# univ_3-1-0-x-rev2.net
KiCad netlist of a schematic drawn in EAGLE
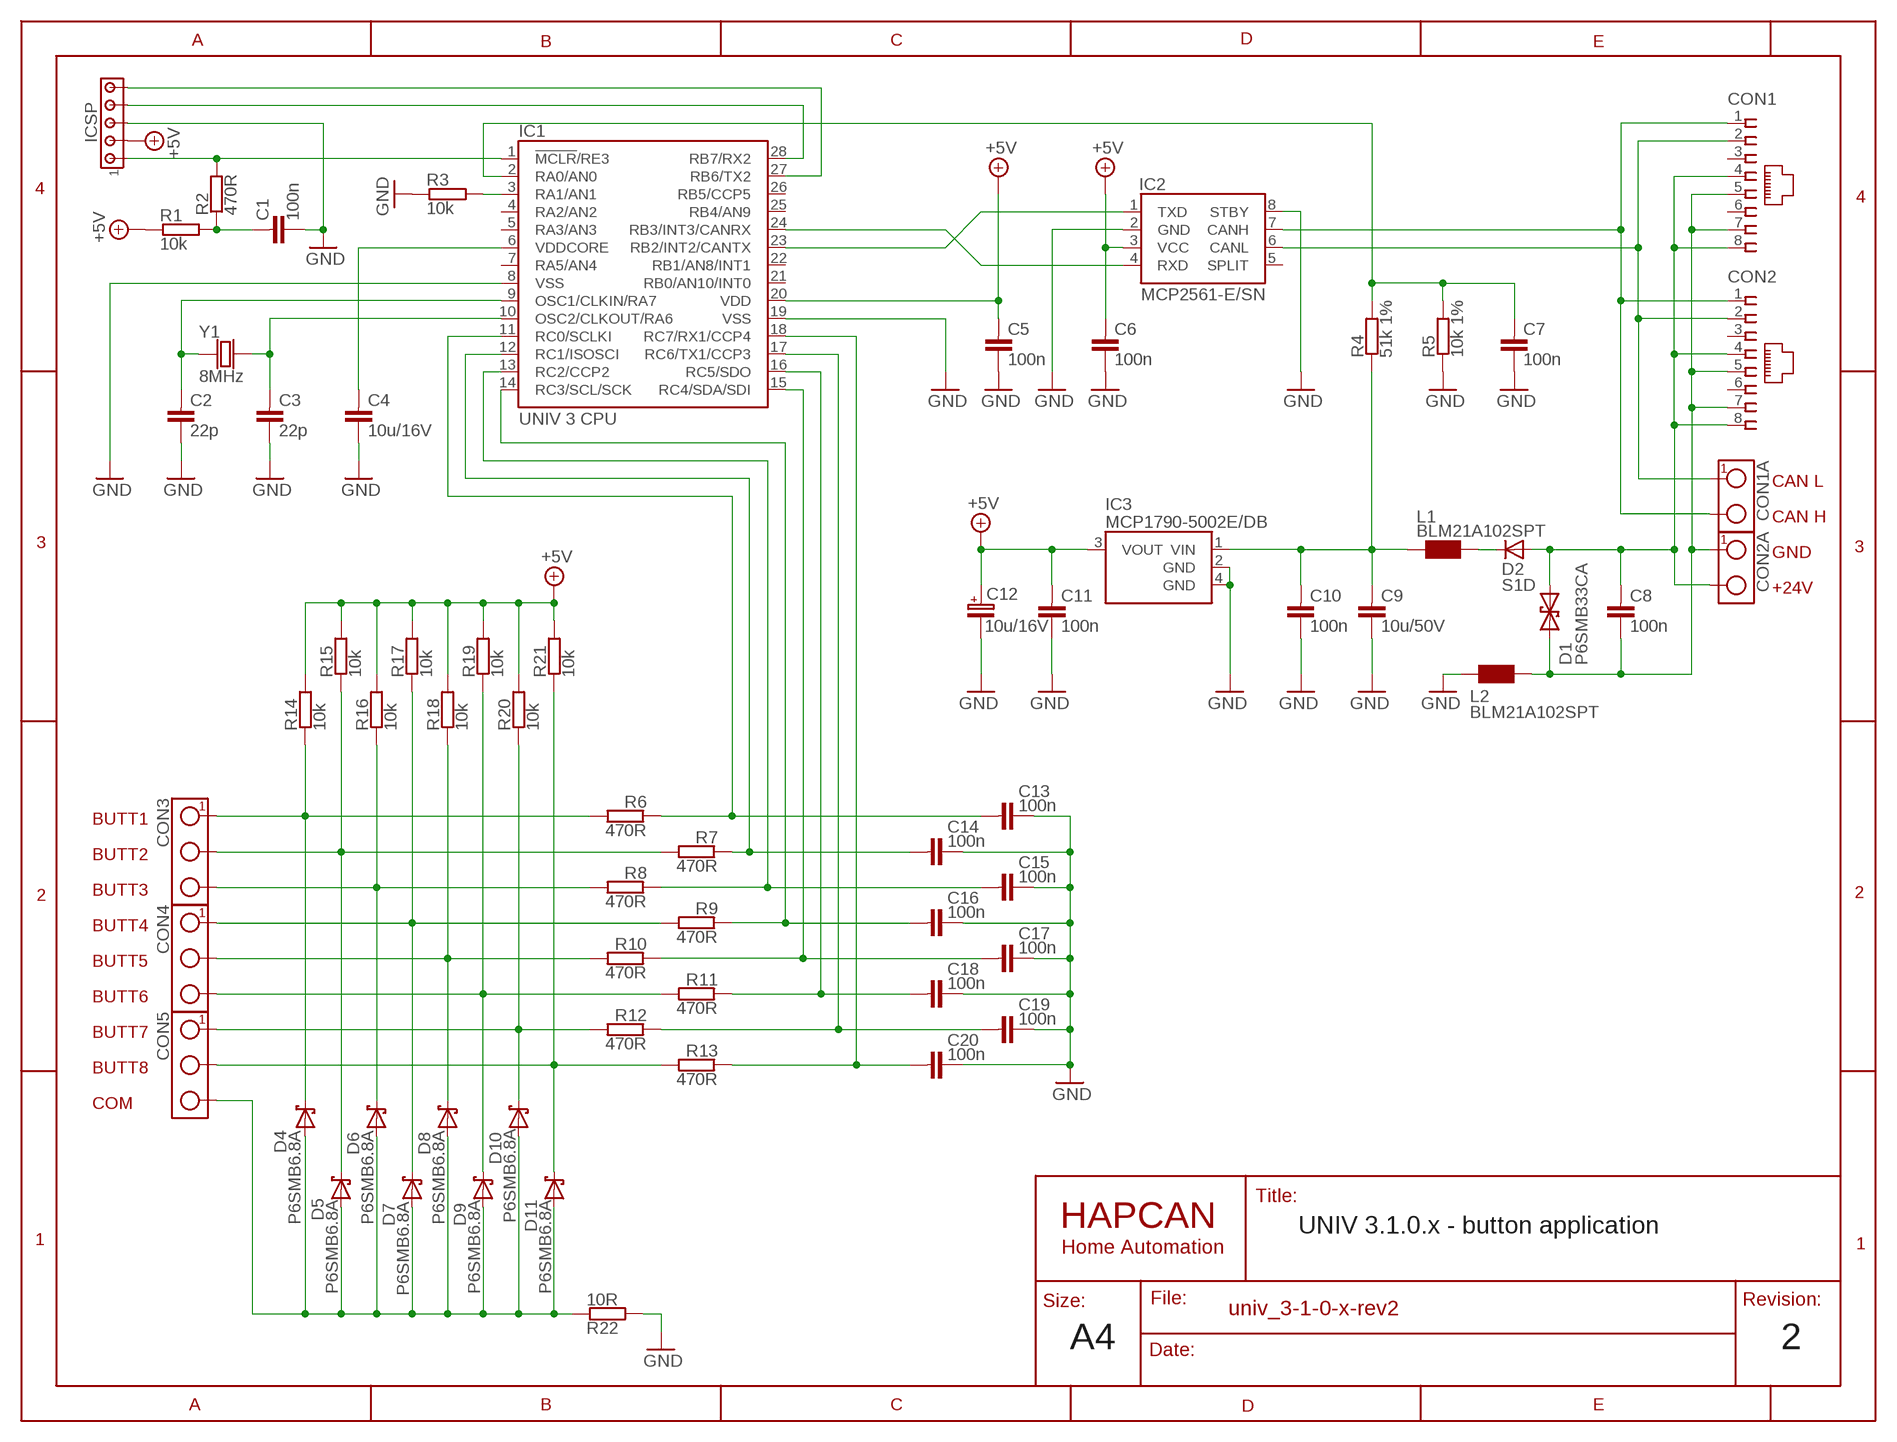
[diagram p0: schematic, sheet 1]

(export (version "E")
  (design (tool "Eeschema 10.0.6"))
  (components
    (comp (ref "C1")
      (value "100n")
      (footprint "eagle-import:0805")
      (libsource (lib "eagle-import") (part "CAPACITOR0805"))
    )
    (comp (ref "C2")
      (value "22p")
      (footprint "eagle-import:0805")
      (libsource (lib "eagle-import") (part "CAPACITOR0805"))
    )
    (comp (ref "C3")
      (value "22p")
      (footprint "eagle-import:0805")
      (libsource (lib "eagle-import") (part "CAPACITOR0805"))
    )
    (comp (ref "C4")
      (value "10u/16V")
      (footprint "eagle-import:0805")
      (libsource (lib "eagle-import") (part "CAPACITOR0805"))
    )
    (comp (ref "C5")
      (value "100n")
      (footprint "eagle-import:0805")
      (libsource (lib "eagle-import") (part "CAPACITOR0805"))
    )
    (comp (ref "C6")
      (value "100n")
      (footprint "eagle-import:0805")
      (libsource (lib "eagle-import") (part "CAPACITOR0805"))
    )
    (comp (ref "C7")
      (value "100n")
      (footprint "eagle-import:0805")
      (libsource (lib "eagle-import") (part "CAPACITOR0805"))
    )
    (comp (ref "C8")
      (value "100n")
      (footprint "eagle-import:0805")
      (libsource (lib "eagle-import") (part "CAPACITOR0805"))
    )
    (comp (ref "C9")
      (value "10u/50V")
      (footprint "eagle-import:1210")
      (libsource (lib "eagle-import") (part "CAPACITOR1210"))
    )
    (comp (ref "C10")
      (value "100n")
      (footprint "eagle-import:0805")
      (libsource (lib "eagle-import") (part "CAPACITOR0805"))
    )
    (comp (ref "C11")
      (value "100n")
      (footprint "eagle-import:0805")
      (libsource (lib "eagle-import") (part "CAPACITOR0805"))
    )
    (comp (ref "C12")
      (value "10u/16V")
      (footprint "eagle-import:SMC_B")
      (libsource (lib "eagle-import") (part "CAPACITOR-POLARIZED-SMC_B"))
    )
    (comp (ref "C13")
      (value "100n")
      (footprint "eagle-import:0805")
      (libsource (lib "eagle-import") (part "CAPACITOR0805"))
    )
    (comp (ref "C14")
      (value "100n")
      (footprint "eagle-import:0805")
      (libsource (lib "eagle-import") (part "CAPACITOR0805"))
    )
    (comp (ref "C15")
      (value "100n")
      (footprint "eagle-import:0805")
      (libsource (lib "eagle-import") (part "CAPACITOR0805"))
    )
    (comp (ref "C16")
      (value "100n")
      (footprint "eagle-import:0805")
      (libsource (lib "eagle-import") (part "CAPACITOR0805"))
    )
    (comp (ref "C17")
      (value "100n")
      (footprint "eagle-import:0805")
      (libsource (lib "eagle-import") (part "CAPACITOR0805"))
    )
    (comp (ref "C18")
      (value "100n")
      (footprint "eagle-import:0805")
      (libsource (lib "eagle-import") (part "CAPACITOR0805"))
    )
    (comp (ref "C19")
      (value "100n")
      (footprint "eagle-import:0805")
      (libsource (lib "eagle-import") (part "CAPACITOR0805"))
    )
    (comp (ref "C20")
      (value "100n")
      (footprint "eagle-import:0805")
      (libsource (lib "eagle-import") (part "CAPACITOR0805"))
    )
    (comp (ref "CON1")
      (value "RJ45-SOCKET")
      (footprint "eagle-import:RJ45-PCB-SOCKET")
      (libsource (lib "eagle-import") (part "RJ45-SOCKET"))
    )
    (comp (ref "CON1A")
      (value "TERMINAL-2")
      (footprint "eagle-import:ARK2-5X10,5MM")
      (libsource (lib "eagle-import") (part "TERMINAL-2-5X10,5MM"))
    )
    (comp (ref "CON2")
      (value "RJ45-SOCKET")
      (footprint "eagle-import:RJ45-PCB-SOCKET")
      (libsource (lib "eagle-import") (part "RJ45-SOCKET"))
    )
    (comp (ref "CON2A")
      (value "TERMINAL-2")
      (footprint "eagle-import:ARK2-5X10,5MM")
      (libsource (lib "eagle-import") (part "TERMINAL-2-5X10,5MM"))
    )
    (comp (ref "CON3")
      (value "TERMINAL-3")
      (footprint "eagle-import:ARK3-5X10.5MM")
      (libsource (lib "eagle-import") (part "TERMINAL-3-5X10.5MM"))
    )
    (comp (ref "CON4")
      (value "TERMINAL-3")
      (footprint "eagle-import:ARK3-5X10.5MM")
      (libsource (lib "eagle-import") (part "TERMINAL-3-5X10.5MM"))
    )
    (comp (ref "CON5")
      (value "TERMINAL-3")
      (footprint "eagle-import:ARK3-5X10.5MM")
      (libsource (lib "eagle-import") (part "TERMINAL-3-5X10.5MM"))
    )
    (comp (ref "D1")
      (value "P6SMB33CA")
      (footprint "eagle-import:DO-214_TRANSIL2")
      (libsource (lib "eagle-import") (part "DIODE_TRANSIL2"))
    )
    (comp (ref "D2")
      (value "S1D")
      (footprint "eagle-import:DO-214")
      (libsource (lib "eagle-import") (part "DIODE_DO-214"))
    )
    (comp (ref "D4")
      (value "P6SMB6.8A")
      (footprint "eagle-import:DO-214")
      (libsource (lib "eagle-import") (part "DIODE_TRANSIL1_DO214"))
    )
    (comp (ref "D5")
      (value "P6SMB6.8A")
      (footprint "eagle-import:DO-214")
      (libsource (lib "eagle-import") (part "DIODE_TRANSIL1_DO214"))
    )
    (comp (ref "D6")
      (value "P6SMB6.8A")
      (footprint "eagle-import:DO-214")
      (libsource (lib "eagle-import") (part "DIODE_TRANSIL1_DO214"))
    )
    (comp (ref "D7")
      (value "P6SMB6.8A")
      (footprint "eagle-import:DO-214")
      (libsource (lib "eagle-import") (part "DIODE_TRANSIL1_DO214"))
    )
    (comp (ref "D8")
      (value "P6SMB6.8A")
      (footprint "eagle-import:DO-214")
      (libsource (lib "eagle-import") (part "DIODE_TRANSIL1_DO214"))
    )
    (comp (ref "D9")
      (value "P6SMB6.8A")
      (footprint "eagle-import:DO-214")
      (libsource (lib "eagle-import") (part "DIODE_TRANSIL1_DO214"))
    )
    (comp (ref "D10")
      (value "P6SMB6.8A")
      (footprint "eagle-import:DO-214")
      (libsource (lib "eagle-import") (part "DIODE_TRANSIL1_DO214"))
    )
    (comp (ref "D11")
      (value "P6SMB6.8A")
      (footprint "eagle-import:DO-214")
      (libsource (lib "eagle-import") (part "DIODE_TRANSIL1_DO214"))
    )
    (comp (ref "IC1")
      (value "UNIV 3 CPU")
      (footprint "eagle-import:UNIV3CPU")
      (libsource (lib "eagle-import") (part "UNIV3CPU-I/SO"))
    )
    (comp (ref "IC2")
      (value "MCP2561-E/SN")
      (footprint "eagle-import:SO-08")
      (libsource (lib "eagle-import") (part "MCP2561-E/SN"))
    )
    (comp (ref "IC3")
      (value "MCP1790-5002E/DB")
      (footprint "eagle-import:SOT-223")
      (libsource (lib "eagle-import") (part "MCP1790"))
    )
    (comp (ref "ICSP")
      (value "HEADER5")
      (footprint "eagle-import:SIP-5")
      (libsource (lib "eagle-import") (part "HEADER5"))
    )
    (comp (ref "L1")
      (value "BLM21A102SPT")
      (footprint "eagle-import:0805")
      (libsource (lib "eagle-import") (part "CHOKE0805"))
    )
    (comp (ref "L2")
      (value "BLM21A102SPT")
      (footprint "eagle-import:0805")
      (libsource (lib "eagle-import") (part "CHOKE0805"))
    )
    (comp (ref "R1")
      (value "10k")
      (footprint "eagle-import:0805")
      (libsource (lib "eagle-import") (part "RESISTOR0805"))
    )
    (comp (ref "R2")
      (value "470R")
      (footprint "eagle-import:0805")
      (libsource (lib "eagle-import") (part "RESISTOR0805"))
    )
    (comp (ref "R3")
      (value "10k")
      (footprint "eagle-import:0805")
      (libsource (lib "eagle-import") (part "RESISTOR0805"))
    )
    (comp (ref "R4")
      (value "51k 1%")
      (footprint "eagle-import:0805")
      (libsource (lib "eagle-import") (part "RESISTOR0805"))
    )
    (comp (ref "R5")
      (value "10k 1%")
      (footprint "eagle-import:0805")
      (libsource (lib "eagle-import") (part "RESISTOR0805"))
    )
    (comp (ref "R6")
      (value "470R")
      (footprint "eagle-import:0805")
      (libsource (lib "eagle-import") (part "RESISTOR0805"))
    )
    (comp (ref "R7")
      (value "470R")
      (footprint "eagle-import:0805")
      (libsource (lib "eagle-import") (part "RESISTOR0805"))
    )
    (comp (ref "R8")
      (value "470R")
      (footprint "eagle-import:0805")
      (libsource (lib "eagle-import") (part "RESISTOR0805"))
    )
    (comp (ref "R9")
      (value "470R")
      (footprint "eagle-import:0805")
      (libsource (lib "eagle-import") (part "RESISTOR0805"))
    )
    (comp (ref "R10")
      (value "470R")
      (footprint "eagle-import:0805")
      (libsource (lib "eagle-import") (part "RESISTOR0805"))
    )
    (comp (ref "R11")
      (value "470R")
      (footprint "eagle-import:0805")
      (libsource (lib "eagle-import") (part "RESISTOR0805"))
    )
    (comp (ref "R12")
      (value "470R")
      (footprint "eagle-import:0805")
      (libsource (lib "eagle-import") (part "RESISTOR0805"))
    )
    (comp (ref "R13")
      (value "470R")
      (footprint "eagle-import:0805")
      (libsource (lib "eagle-import") (part "RESISTOR0805"))
    )
    (comp (ref "R14")
      (value "10k")
      (footprint "eagle-import:0805")
      (libsource (lib "eagle-import") (part "RESISTOR0805"))
    )
    (comp (ref "R15")
      (value "10k")
      (footprint "eagle-import:0805")
      (libsource (lib "eagle-import") (part "RESISTOR0805"))
    )
    (comp (ref "R16")
      (value "10k")
      (footprint "eagle-import:0805")
      (libsource (lib "eagle-import") (part "RESISTOR0805"))
    )
    (comp (ref "R17")
      (value "10k")
      (footprint "eagle-import:0805")
      (libsource (lib "eagle-import") (part "RESISTOR0805"))
    )
    (comp (ref "R18")
      (value "10k")
      (footprint "eagle-import:0805")
      (libsource (lib "eagle-import") (part "RESISTOR0805"))
    )
    (comp (ref "R19")
      (value "10k")
      (footprint "eagle-import:0805")
      (libsource (lib "eagle-import") (part "RESISTOR0805"))
    )
    (comp (ref "R20")
      (value "10k")
      (footprint "eagle-import:0805")
      (libsource (lib "eagle-import") (part "RESISTOR0805"))
    )
    (comp (ref "R21")
      (value "10k")
      (footprint "eagle-import:0805")
      (libsource (lib "eagle-import") (part "RESISTOR0805"))
    )
    (comp (ref "R22")
      (value "10R")
      (footprint "eagle-import:0805")
      (libsource (lib "eagle-import") (part "RESISTOR0805"))
    )
    (comp (ref "Y1")
      (value "8MHz")
      (footprint "eagle-import:CRYSTAL-HC49V")
      (libsource (lib "eagle-import") (part "CRYSTAL-HC49V"))
    )
  )
  (nets
    (net (code "1") (name "+5V") (class "Default")
      (node (ref "C11") (pin "1") (pinfunction "1_1") (pintype "passive"))
      (node (ref "C12") (pin "+") (pinfunction "1_+") (pintype "passive"))
      (node (ref "C5") (pin "1") (pinfunction "1_1") (pintype "passive"))
      (node (ref "C6") (pin "1") (pinfunction "1_1") (pintype "passive"))
      (node (ref "IC1") (pin "20") (pinfunction "VDD_20") (pintype "bidirectional"))
      (node (ref "IC2") (pin "3") (pinfunction "VCC_3") (pintype "bidirectional"))
      (node (ref "IC3") (pin "3") (pinfunction "VOUT_3") (pintype "bidirectional"))
      (node (ref "ICSP") (pin "2") (pinfunction "2_2") (pintype "passive"))
      (node (ref "R1") (pin "1") (pinfunction "1_1") (pintype "passive"))
      (node (ref "R14") (pin "2") (pinfunction "2_2") (pintype "passive"))
      (node (ref "R15") (pin "2") (pinfunction "2_2") (pintype "passive"))
      (node (ref "R16") (pin "2") (pinfunction "2_2") (pintype "passive"))
      (node (ref "R17") (pin "2") (pinfunction "2_2") (pintype "passive"))
      (node (ref "R18") (pin "2") (pinfunction "2_2") (pintype "passive"))
      (node (ref "R19") (pin "2") (pinfunction "2_2") (pintype "passive"))
      (node (ref "R20") (pin "2") (pinfunction "2_2") (pintype "passive"))
      (node (ref "R21") (pin "2") (pinfunction "2_2") (pintype "passive"))
    )
    (net (code "2") (name "GND") (class "Default")
      (node (ref "C1") (pin "2") (pinfunction "2_2") (pintype "passive"))
      (node (ref "C10") (pin "2") (pinfunction "2_2") (pintype "passive"))
      (node (ref "C11") (pin "2") (pinfunction "2_2") (pintype "passive"))
      (node (ref "C12") (pin "-") (pinfunction "2_-") (pintype "passive"))
      (node (ref "C13") (pin "2") (pinfunction "2_2") (pintype "passive"))
      (node (ref "C14") (pin "2") (pinfunction "2_2") (pintype "passive"))
      (node (ref "C15") (pin "2") (pinfunction "2_2") (pintype "passive"))
      (node (ref "C16") (pin "2") (pinfunction "2_2") (pintype "passive"))
      (node (ref "C17") (pin "2") (pinfunction "2_2") (pintype "passive"))
      (node (ref "C18") (pin "2") (pinfunction "2_2") (pintype "passive"))
      (node (ref "C19") (pin "2") (pinfunction "2_2") (pintype "passive"))
      (node (ref "C2") (pin "2") (pinfunction "2_2") (pintype "passive"))
      (node (ref "C20") (pin "2") (pinfunction "2_2") (pintype "passive"))
      (node (ref "C3") (pin "2") (pinfunction "2_2") (pintype "passive"))
      (node (ref "C4") (pin "2") (pinfunction "2_2") (pintype "passive"))
      (node (ref "C5") (pin "2") (pinfunction "2_2") (pintype "passive"))
      (node (ref "C6") (pin "2") (pinfunction "2_2") (pintype "passive"))
      (node (ref "C7") (pin "2") (pinfunction "2_2") (pintype "passive"))
      (node (ref "C9") (pin "2") (pinfunction "2_2") (pintype "passive"))
      (node (ref "IC1") (pin "19") (pinfunction "VSS_19") (pintype "bidirectional"))
      (node (ref "IC1") (pin "8") (pinfunction "VSS_8") (pintype "bidirectional"))
      (node (ref "IC2") (pin "2") (pinfunction "GND_2") (pintype "bidirectional"))
      (node (ref "IC2") (pin "8") (pinfunction "STBY_8") (pintype "bidirectional"))
      (node (ref "IC3") (pin "2") (pinfunction "GND_2") (pintype "bidirectional"))
      (node (ref "IC3") (pin "4") (pinfunction "GND_4") (pintype "bidirectional"))
      (node (ref "ICSP") (pin "3") (pinfunction "3_3") (pintype "passive"))
      (node (ref "L2") (pin "1") (pinfunction "1_1") (pintype "passive"))
      (node (ref "R22") (pin "2") (pinfunction "2_2") (pintype "passive"))
      (node (ref "R3") (pin "1") (pinfunction "1_1") (pintype "passive"))
      (node (ref "R5") (pin "1") (pinfunction "1_1") (pintype "passive"))
    )
    (net (code "3") (name "Net-(C1-Pad1)") (class "Default")
      (node (ref "C1") (pin "1") (pinfunction "1_1") (pintype "passive"))
      (node (ref "R1") (pin "2") (pinfunction "2_2") (pintype "passive"))
      (node (ref "R2") (pin "1") (pinfunction "1_1") (pintype "passive"))
    )
    (net (code "4") (name "Net-(CON3-Pad1)") (class "Default")
      (node (ref "CON3") (pin "1") (pinfunction "1_1") (pintype "passive"))
      (node (ref "D4") (pin "C") (pinfunction "C_C") (pintype "passive"))
      (node (ref "R14") (pin "1") (pinfunction "1_1") (pintype "passive"))
      (node (ref "R6") (pin "2") (pinfunction "2_2") (pintype "passive"))
    )
    (net (code "5") (name "Net-(CON3-Pad2)") (class "Default")
      (node (ref "CON3") (pin "2") (pinfunction "2_2") (pintype "passive"))
      (node (ref "D5") (pin "C") (pinfunction "C_C") (pintype "passive"))
      (node (ref "R15") (pin "1") (pinfunction "1_1") (pintype "passive"))
      (node (ref "R7") (pin "2") (pinfunction "2_2") (pintype "passive"))
    )
    (net (code "6") (name "Net-(CON3-Pad3)") (class "Default")
      (node (ref "CON3") (pin "3") (pinfunction "3_3") (pintype "passive"))
      (node (ref "D6") (pin "C") (pinfunction "C_C") (pintype "passive"))
      (node (ref "R16") (pin "1") (pinfunction "1_1") (pintype "passive"))
      (node (ref "R8") (pin "2") (pinfunction "2_2") (pintype "passive"))
    )
    (net (code "7") (name "Net-(CON4-Pad1)") (class "Default")
      (node (ref "CON4") (pin "1") (pinfunction "1_1") (pintype "passive"))
      (node (ref "D7") (pin "C") (pinfunction "C_C") (pintype "passive"))
      (node (ref "R17") (pin "1") (pinfunction "1_1") (pintype "passive"))
      (node (ref "R9") (pin "2") (pinfunction "2_2") (pintype "passive"))
    )
    (net (code "8") (name "Net-(CON4-Pad2)") (class "Default")
      (node (ref "CON4") (pin "2") (pinfunction "2_2") (pintype "passive"))
      (node (ref "D8") (pin "C") (pinfunction "C_C") (pintype "passive"))
      (node (ref "R10") (pin "2") (pinfunction "2_2") (pintype "passive"))
      (node (ref "R18") (pin "1") (pinfunction "1_1") (pintype "passive"))
    )
    (net (code "9") (name "Net-(CON4-Pad3)") (class "Default")
      (node (ref "CON4") (pin "3") (pinfunction "3_3") (pintype "passive"))
      (node (ref "D9") (pin "C") (pinfunction "C_C") (pintype "passive"))
      (node (ref "R11") (pin "2") (pinfunction "2_2") (pintype "passive"))
      (node (ref "R19") (pin "1") (pinfunction "1_1") (pintype "passive"))
    )
    (net (code "10") (name "Net-(CON5-Pad1)") (class "Default")
      (node (ref "CON5") (pin "1") (pinfunction "1_1") (pintype "passive"))
      (node (ref "D10") (pin "C") (pinfunction "C_C") (pintype "passive"))
      (node (ref "R12") (pin "2") (pinfunction "2_2") (pintype "passive"))
      (node (ref "R20") (pin "1") (pinfunction "1_1") (pintype "passive"))
    )
    (net (code "11") (name "Net-(CON5-Pad2)") (class "Default")
      (node (ref "CON5") (pin "2") (pinfunction "2_2") (pintype "passive"))
      (node (ref "D11") (pin "C") (pinfunction "C_C") (pintype "passive"))
      (node (ref "R13") (pin "2") (pinfunction "2_2") (pintype "passive"))
      (node (ref "R21") (pin "1") (pinfunction "1_1") (pintype "passive"))
    )
    (net (code "12") (name "Net-(CON5-Pad3)") (class "Default")
      (node (ref "CON5") (pin "3") (pinfunction "3_3") (pintype "passive"))
      (node (ref "D10") (pin "A") (pinfunction "A_A") (pintype "passive"))
      (node (ref "D11") (pin "A") (pinfunction "A_A") (pintype "passive"))
      (node (ref "D4") (pin "A") (pinfunction "A_A") (pintype "passive"))
      (node (ref "D5") (pin "A") (pinfunction "A_A") (pintype "passive"))
      (node (ref "D6") (pin "A") (pinfunction "A_A") (pintype "passive"))
      (node (ref "D7") (pin "A") (pinfunction "A_A") (pintype "passive"))
      (node (ref "D8") (pin "A") (pinfunction "A_A") (pintype "passive"))
      (node (ref "D9") (pin "A") (pinfunction "A_A") (pintype "passive"))
      (node (ref "R22") (pin "1") (pinfunction "1_1") (pintype "passive"))
    )
    (net (code "13") (name "Net-(D1-1)") (class "Default")
      (node (ref "C8") (pin "1") (pinfunction "1_1") (pintype "passive"))
      (node (ref "CON1") (pin "4") (pinfunction "4_4") (pintype "passive"))
      (node (ref "CON1") (pin "8") (pinfunction "8_8") (pintype "passive"))
      (node (ref "CON2") (pin "4") (pinfunction "4_4") (pintype "passive"))
      (node (ref "CON2") (pin "8") (pinfunction "8_8") (pintype "passive"))
      (node (ref "CON2A") (pin "2") (pinfunction "2_2") (pintype "passive"))
      (node (ref "D1") (pin "A") (pinfunction "1_A") (pintype "passive"))
      (node (ref "D2") (pin "A") (pinfunction "A_A") (pintype "passive"))
    )
    (net (code "14") (name "Net-(D1-2)") (class "Default")
      (node (ref "C8") (pin "2") (pinfunction "2_2") (pintype "passive"))
      (node (ref "CON1") (pin "5") (pinfunction "5_5") (pintype "passive"))
      (node (ref "CON1") (pin "7") (pinfunction "7_7") (pintype "passive"))
      (node (ref "CON2") (pin "5") (pinfunction "5_5") (pintype "passive"))
      (node (ref "CON2") (pin "7") (pinfunction "7_7") (pintype "passive"))
      (node (ref "CON2A") (pin "1") (pinfunction "1_1") (pintype "passive"))
      (node (ref "D1") (pin "C") (pinfunction "2_C") (pintype "passive"))
      (node (ref "L2") (pin "2") (pinfunction "2_2") (pintype "passive"))
    )
    (net (code "15") (name "Net-(D2-PadC)") (class "Default")
      (node (ref "D2") (pin "C") (pinfunction "C_C") (pintype "passive"))
      (node (ref "L1") (pin "2") (pinfunction "2_2") (pintype "passive"))
    )
    (net (code "16") (name "Net-(IC1-OSC1{slash}CLKIN{slash}RA7)") (class "Default")
      (node (ref "C2") (pin "1") (pinfunction "1_1") (pintype "passive"))
      (node (ref "IC1") (pin "9") (pinfunction "OSC1/CLKIN/RA7_9") (pintype "bidirectional"))
      (node (ref "Y1") (pin "1") (pinfunction "1_1") (pintype "passive"))
    )
    (net (code "17") (name "Net-(IC1-OSC2{slash}CLKOUT{slash}RA6)") (class "Default")
      (node (ref "C3") (pin "1") (pinfunction "1_1") (pintype "passive"))
      (node (ref "IC1") (pin "10") (pinfunction "OSC2/CLKOUT/RA6_10") (pintype "bidirectional"))
      (node (ref "Y1") (pin "2") (pinfunction "2_2") (pintype "passive"))
    )
    (net (code "18") (name "Net-(IC1-RA0{slash}AN0)") (class "Default")
      (node (ref "C7") (pin "1") (pinfunction "1_1") (pintype "passive"))
      (node (ref "IC1") (pin "2") (pinfunction "RA0/AN0_2") (pintype "bidirectional"))
      (node (ref "R4") (pin "2") (pinfunction "2_2") (pintype "passive"))
      (node (ref "R5") (pin "2") (pinfunction "2_2") (pintype "passive"))
    )
    (net (code "19") (name "Net-(IC1-RA1{slash}AN1)") (class "Default")
      (node (ref "IC1") (pin "3") (pinfunction "RA1/AN1_3") (pintype "bidirectional"))
      (node (ref "R3") (pin "2") (pinfunction "2_2") (pintype "passive"))
    )
    (net (code "20") (name "Net-(IC1-RB2{slash}INT2{slash}CANTX)") (class "Default")
      (node (ref "IC1") (pin "23") (pinfunction "RB2/INT2/CANTX_23") (pintype "bidirectional"))
      (node (ref "IC2") (pin "1") (pinfunction "TXD_1") (pintype "bidirectional"))
    )
    (net (code "21") (name "Net-(IC1-RB3{slash}INT3{slash}CANRX)") (class "Default")
      (node (ref "IC1") (pin "24") (pinfunction "RB3/INT3/CANRX_24") (pintype "bidirectional"))
      (node (ref "IC2") (pin "4") (pinfunction "RXD_4") (pintype "bidirectional"))
    )
    (net (code "22") (name "Net-(IC1-RB6{slash}TX2)") (class "Default")
      (node (ref "IC1") (pin "27") (pinfunction "RB6/TX2_27") (pintype "bidirectional"))
      (node (ref "ICSP") (pin "5") (pinfunction "5_5") (pintype "passive"))
    )
    (net (code "23") (name "Net-(IC1-RB7{slash}RX2)") (class "Default")
      (node (ref "IC1") (pin "28") (pinfunction "RB7/RX2_28") (pintype "bidirectional"))
      (node (ref "ICSP") (pin "4") (pinfunction "4_4") (pintype "passive"))
    )
    (net (code "24") (name "Net-(IC1-RC0{slash}SCLKI)") (class "Default")
      (node (ref "C13") (pin "1") (pinfunction "1_1") (pintype "passive"))
      (node (ref "IC1") (pin "11") (pinfunction "RC0/SCLKI_11") (pintype "bidirectional"))
      (node (ref "R6") (pin "1") (pinfunction "1_1") (pintype "passive"))
    )
    (net (code "25") (name "Net-(IC1-RC1{slash}ISOSCI)") (class "Default")
      (node (ref "C14") (pin "1") (pinfunction "1_1") (pintype "passive"))
      (node (ref "IC1") (pin "12") (pinfunction "RC1/ISOSCI_12") (pintype "bidirectional"))
      (node (ref "R7") (pin "1") (pinfunction "1_1") (pintype "passive"))
    )
    (net (code "26") (name "Net-(IC1-RC2{slash}CCP2)") (class "Default")
      (node (ref "C15") (pin "1") (pinfunction "1_1") (pintype "passive"))
      (node (ref "IC1") (pin "13") (pinfunction "RC2/CCP2_13") (pintype "bidirectional"))
      (node (ref "R8") (pin "1") (pinfunction "1_1") (pintype "passive"))
    )
    (net (code "27") (name "Net-(IC1-RC3{slash}SCL{slash}SCK)") (class "Default")
      (node (ref "C16") (pin "1") (pinfunction "1_1") (pintype "passive"))
      (node (ref "IC1") (pin "14") (pinfunction "RC3/SCL/SCK_14") (pintype "bidirectional"))
      (node (ref "R9") (pin "1") (pinfunction "1_1") (pintype "passive"))
    )
    (net (code "28") (name "Net-(IC1-RC4{slash}SDA{slash}SDI)") (class "Default")
      (node (ref "C17") (pin "1") (pinfunction "1_1") (pintype "passive"))
      (node (ref "IC1") (pin "15") (pinfunction "RC4/SDA/SDI_15") (pintype "bidirectional"))
      (node (ref "R10") (pin "1") (pinfunction "1_1") (pintype "passive"))
    )
    (net (code "29") (name "Net-(IC1-RC5{slash}SDO)") (class "Default")
      (node (ref "C18") (pin "1") (pinfunction "1_1") (pintype "passive"))
      (node (ref "IC1") (pin "16") (pinfunction "RC5/SDO_16") (pintype "bidirectional"))
      (node (ref "R11") (pin "1") (pinfunction "1_1") (pintype "passive"))
    )
    (net (code "30") (name "Net-(IC1-RC6{slash}TX1{slash}CCP3)") (class "Default")
      (node (ref "C19") (pin "1") (pinfunction "1_1") (pintype "passive"))
      (node (ref "IC1") (pin "17") (pinfunction "RC6/TX1/CCP3_17") (pintype "bidirectional"))
      (node (ref "R12") (pin "1") (pinfunction "1_1") (pintype "passive"))
    )
    (net (code "31") (name "Net-(IC1-RC7{slash}RX1{slash}CCP4)") (class "Default")
      (node (ref "C20") (pin "1") (pinfunction "1_1") (pintype "passive"))
      (node (ref "IC1") (pin "18") (pinfunction "RC7/RX1/CCP4_18") (pintype "bidirectional"))
      (node (ref "R13") (pin "1") (pinfunction "1_1") (pintype "passive"))
    )
    (net (code "32") (name "Net-(IC1-VDDCORE)") (class "Default")
      (node (ref "C4") (pin "1") (pinfunction "1_1") (pintype "passive"))
      (node (ref "IC1") (pin "6") (pinfunction "VDDCORE_6") (pintype "bidirectional"))
    )
    (net (code "33") (name "Net-(IC1-~{MCLR}{slash}RE3)") (class "Default")
      (node (ref "IC1") (pin "1") (pinfunction "~{MCLR}/RE3_1") (pintype "bidirectional"))
      (node (ref "ICSP") (pin "1") (pinfunction "1_1") (pintype "passive"))
      (node (ref "R2") (pin "2") (pinfunction "2_2") (pintype "passive"))
    )
    (net (code "34") (name "Net-(IC2-CANH)") (class "Default")
      (node (ref "CON1") (pin "1") (pinfunction "1_1") (pintype "passive"))
      (node (ref "CON1A") (pin "2") (pinfunction "2_2") (pintype "passive"))
      (node (ref "CON2") (pin "1") (pinfunction "1_1") (pintype "passive"))
      (node (ref "IC2") (pin "7") (pinfunction "CANH_7") (pintype "bidirectional"))
    )
    (net (code "35") (name "Net-(IC2-CANL)") (class "Default")
      (node (ref "CON1") (pin "2") (pinfunction "2_2") (pintype "passive"))
      (node (ref "CON1A") (pin "1") (pinfunction "1_1") (pintype "passive"))
      (node (ref "CON2") (pin "2") (pinfunction "2_2") (pintype "passive"))
      (node (ref "IC2") (pin "6") (pinfunction "CANL_6") (pintype "bidirectional"))
    )
    (net (code "36") (name "Net-(IC3-VIN)") (class "Default")
      (node (ref "C10") (pin "1") (pinfunction "1_1") (pintype "passive"))
      (node (ref "C9") (pin "1") (pinfunction "1_1") (pintype "passive"))
      (node (ref "IC3") (pin "1") (pinfunction "VIN_1") (pintype "bidirectional"))
      (node (ref "L1") (pin "1") (pinfunction "1_1") (pintype "passive"))
      (node (ref "R4") (pin "1") (pinfunction "1_1") (pintype "passive"))
    )
    (net (code "37") (name "unconnected-(CON1-Pad3)") (class "Default")
      (node (ref "CON1") (pin "3") (pinfunction "3_3") (pintype "passive"))
    )
    (net (code "38") (name "unconnected-(CON1-Pad6)") (class "Default")
      (node (ref "CON1") (pin "6") (pinfunction "6_6") (pintype "passive"))
    )
    (net (code "39") (name "unconnected-(CON2-Pad3)") (class "Default")
      (node (ref "CON2") (pin "3") (pinfunction "3_3") (pintype "passive"))
    )
    (net (code "40") (name "unconnected-(CON2-Pad6)") (class "Default")
      (node (ref "CON2") (pin "6") (pinfunction "6_6") (pintype "passive"))
    )
    (net (code "41") (name "unconnected-(IC1-RA2{slash}AN2-Pad4)") (class "Default")
      (node (ref "IC1") (pin "4") (pinfunction "RA2/AN2_4") (pintype "bidirectional"))
    )
    (net (code "42") (name "unconnected-(IC1-RA3{slash}AN3-Pad5)") (class "Default")
      (node (ref "IC1") (pin "5") (pinfunction "RA3/AN3_5") (pintype "bidirectional"))
    )
    (net (code "43") (name "unconnected-(IC1-RA5{slash}AN4-Pad7)") (class "Default")
      (node (ref "IC1") (pin "7") (pinfunction "RA5/AN4_7") (pintype "bidirectional"))
    )
    (net (code "44") (name "unconnected-(IC1-RB0{slash}AN10{slash}INT0-Pad21)") (class "Default")
      (node (ref "IC1") (pin "21") (pinfunction "RB0/AN10/INT0_21") (pintype "bidirectional"))
    )
    (net (code "45") (name "unconnected-(IC1-RB1{slash}AN8{slash}INT1-Pad22)") (class "Default")
      (node (ref "IC1") (pin "22") (pinfunction "RB1/AN8/INT1_22") (pintype "bidirectional"))
    )
    (net (code "46") (name "unconnected-(IC1-RB4{slash}AN9-Pad25)") (class "Default")
      (node (ref "IC1") (pin "25") (pinfunction "RB4/AN9_25") (pintype "bidirectional"))
    )
    (net (code "47") (name "unconnected-(IC1-RB5{slash}CCP5-Pad26)") (class "Default")
      (node (ref "IC1") (pin "26") (pinfunction "RB5/CCP5_26") (pintype "bidirectional"))
    )
    (net (code "48") (name "unconnected-(IC2-SPLIT-Pad5)") (class "Default")
      (node (ref "IC2") (pin "5") (pinfunction "SPLIT_5") (pintype "bidirectional"))
    )
  )
)
